# 10_USB_HDMI.net
KiCad netlist of a schematic drawn in Altium Designer
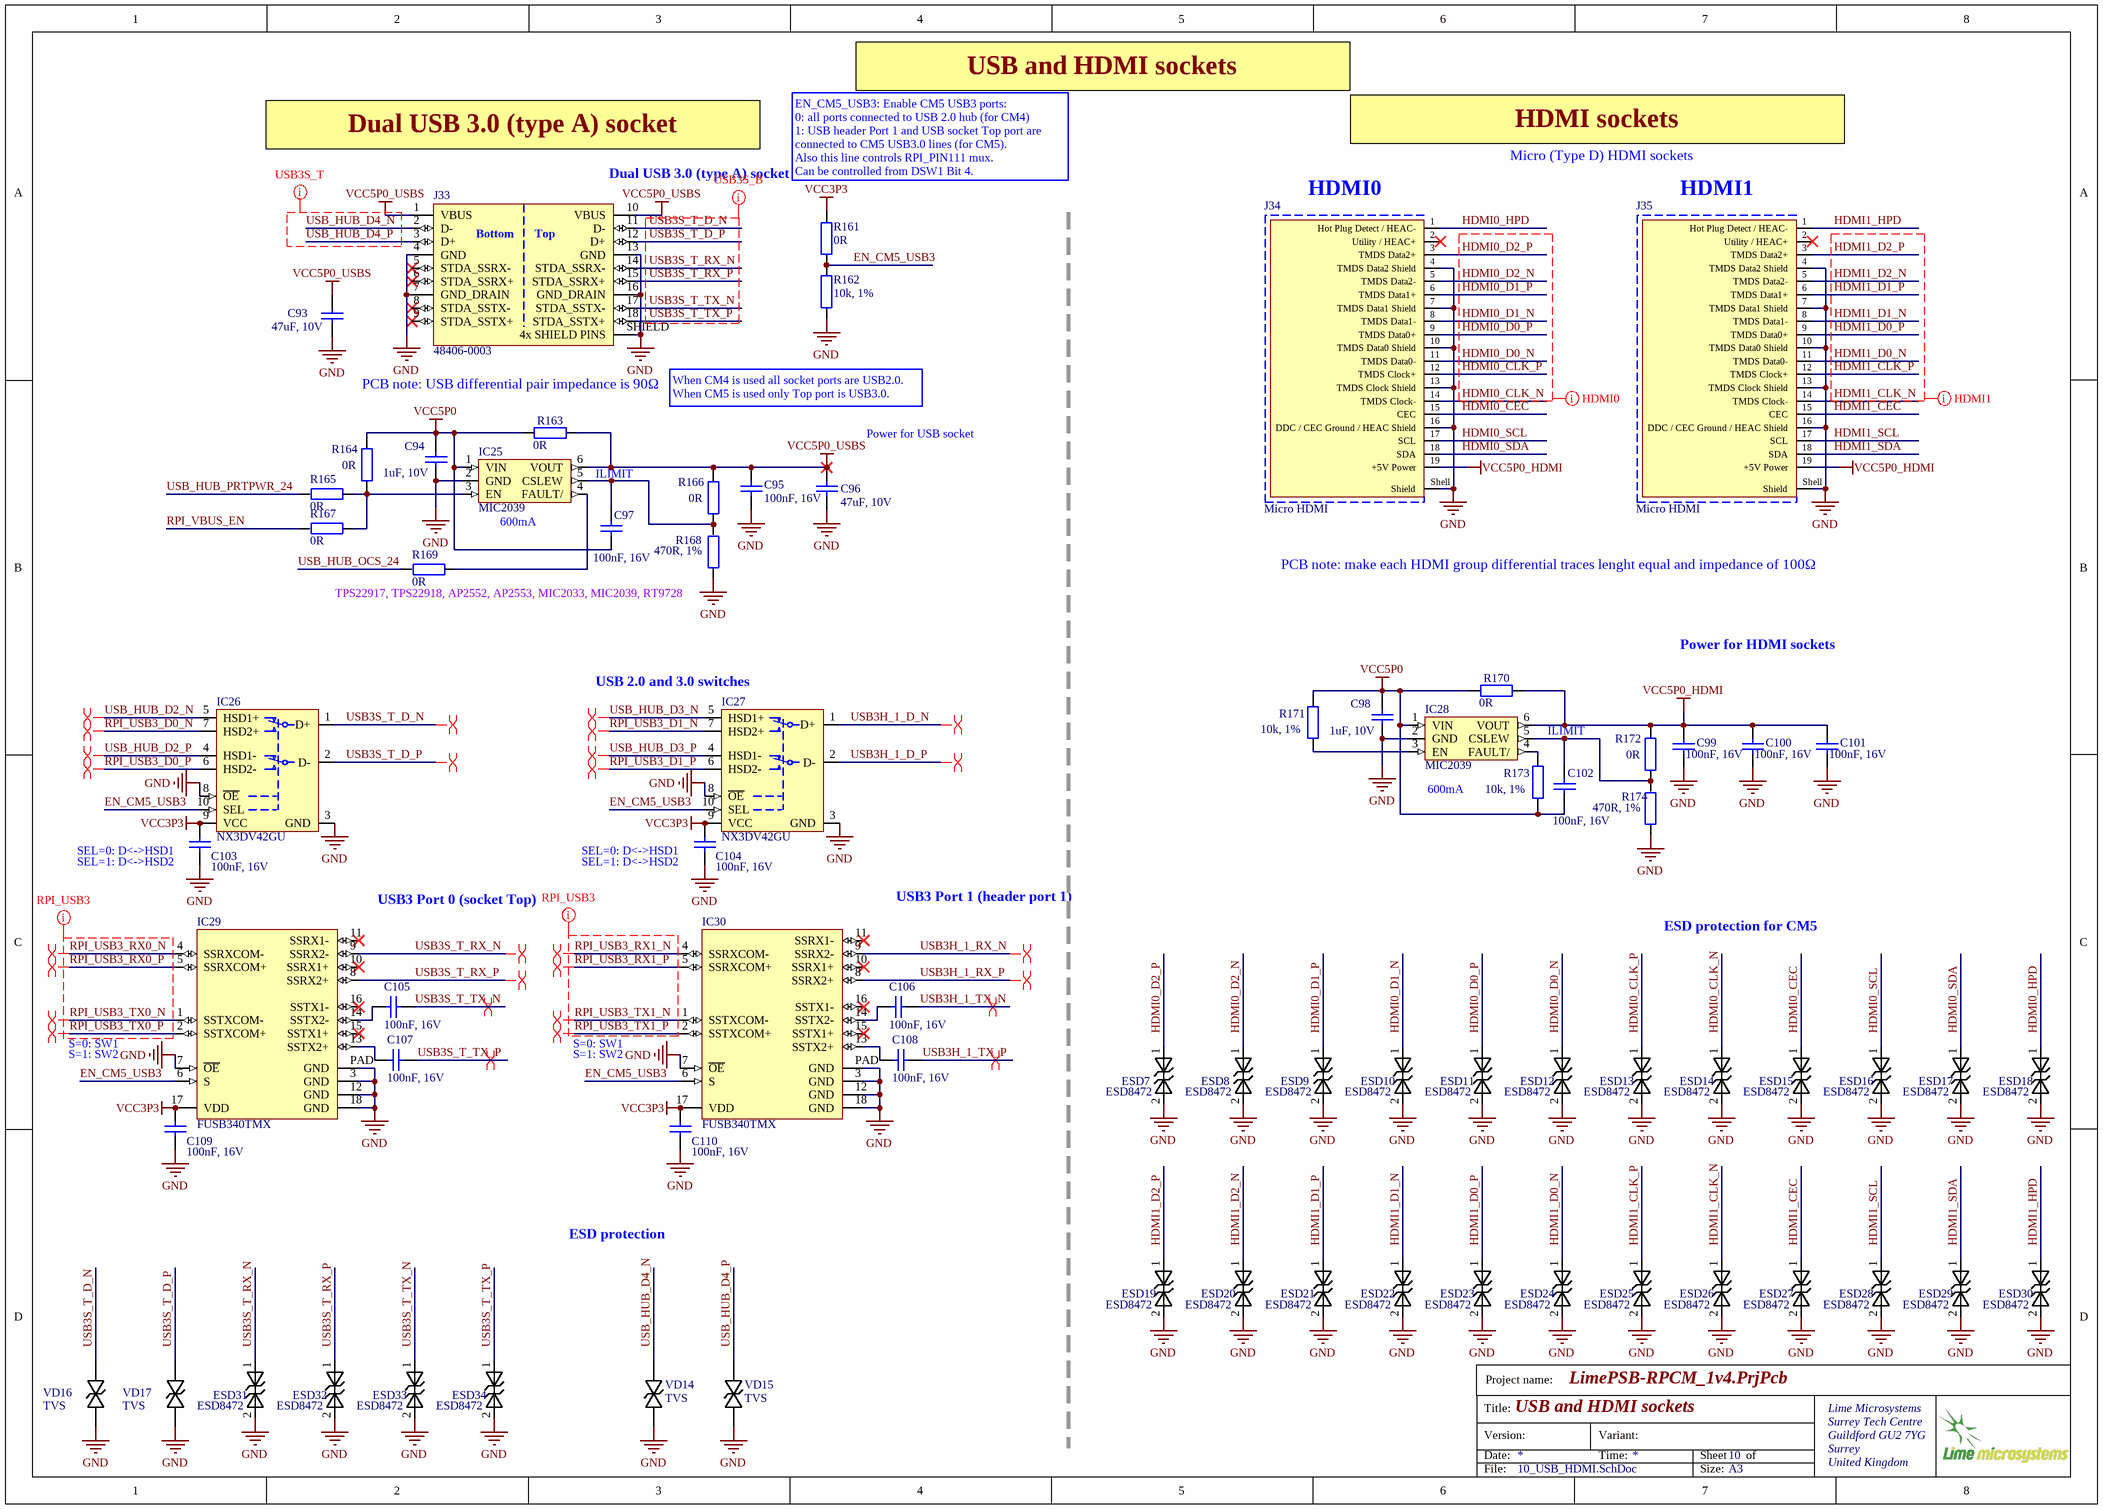
[diagram p0: 10_USB_HDMI.SchDoc]

(export (version "E")
  (design (tool "Eeschema 10.0.6"))
  (components
    (comp (ref "C93")
      (value "47uF, 10V")
      (footprint "CAP1206")
      (fields (field (name "TOLERANCE") "±20%") (field (name "MANUFACTURER") "TDK Corporation"))
      (libsource (lib "LimeFPGAboard_schLib") (part "Cap_1206"))
    )
    (comp (ref "C94")
      (value "1uF, 10V")
      (footprint "CAP0402")
      (fields (field (name "MANUFACTURER") "Yageo"))
      (libsource (lib "") (part "Cap_0402_1"))
    )
    (comp (ref "C95")
      (value "100nF, 16V")
      (footprint "CAP0402")
      (fields
        (field (name "MANUFACTURER") "Murata Electronics")
        (field (name "TOLERANCE") "10 %")
        (field (name "MANUFACTURER PART NUMBER") "GRM155R71C104KA88D")
      )
      (libsource (lib "") (part "Cap_0402_1"))
    )
    (comp (ref "C96")
      (value "47uF, 10V")
      (footprint "CAP1206")
      (fields (field (name "TOLERANCE") "±20%") (field (name "MANUFACTURER") "TDK Corporation"))
      (libsource (lib "LimeFPGAboard_schLib") (part "Cap_1206"))
    )
    (comp (ref "C97")
      (value "100nF, 16V")
      (footprint "CAP0402")
      (fields
        (field (name "MANUFACTURER") "Murata Electronics")
        (field (name "TOLERANCE") "10 %")
        (field (name "MANUFACTURER PART NUMBER") "GRM155R71C104KA88D")
      )
      (libsource (lib "") (part "Cap_0402_1"))
    )
    (comp (ref "C98")
      (value "1uF, 10V")
      (footprint "CAP0402")
      (fields (field (name "MANUFACTURER") "Yageo"))
      (libsource (lib "") (part "Cap_0402_1"))
    )
    (comp (ref "C99")
      (value "100nF, 16V")
      (footprint "CAP0402")
      (fields
        (field (name "MANUFACTURER") "Murata Electronics")
        (field (name "TOLERANCE") "10 %")
        (field (name "MANUFACTURER PART NUMBER") "GRM155R71C104KA88D")
      )
      (libsource (lib "") (part "Cap_0402_1"))
    )
    (comp (ref "C100")
      (value "100nF, 16V")
      (footprint "CAP0402")
      (fields
        (field (name "MANUFACTURER") "Murata Electronics")
        (field (name "TOLERANCE") "10 %")
        (field (name "MANUFACTURER PART NUMBER") "GRM155R71C104KA88D")
      )
      (libsource (lib "") (part "Cap_0402_1"))
    )
    (comp (ref "C101")
      (value "100nF, 16V")
      (footprint "CAP0402")
      (fields
        (field (name "MANUFACTURER") "Murata Electronics")
        (field (name "TOLERANCE") "10 %")
        (field (name "MANUFACTURER PART NUMBER") "GRM155R71C104KA88D")
      )
      (libsource (lib "") (part "Cap_0402_1"))
    )
    (comp (ref "C102")
      (value "100nF, 16V")
      (footprint "CAP0402")
      (fields
        (field (name "MANUFACTURER") "Murata Electronics")
        (field (name "TOLERANCE") "10 %")
        (field (name "MANUFACTURER PART NUMBER") "GRM155R71C104KA88D")
      )
      (libsource (lib "") (part "Cap_0402_1"))
    )
    (comp (ref "C103")
      (value "100nF, 16V")
      (footprint "CAP0402")
      (fields
        (field (name "MANUFACTURER") "Murata Electronics")
        (field (name "TOLERANCE") "10 %")
        (field (name "MANUFACTURER PART NUMBER") "GRM155R71C104KA88D")
      )
      (libsource (lib "LimeMicroAltiumLib_schLib") (part "Cap_0402"))
    )
    (comp (ref "C104")
      (value "100nF, 16V")
      (footprint "CAP0402")
      (fields
        (field (name "MANUFACTURER") "Murata Electronics")
        (field (name "TOLERANCE") "10 %")
        (field (name "MANUFACTURER PART NUMBER") "GRM155R71C104KA88D")
      )
      (libsource (lib "LimeMicroAltiumLib_schLib") (part "Cap_0402"))
    )
    (comp (ref "C105")
      (value "100nF, 16V")
      (footprint "CAP0402")
      (fields
        (field (name "MANUFACTURER") "Murata Electronics")
        (field (name "TOLERANCE") "10 %")
        (field (name "MANUFACTURER PART NUMBER") "GRM155R71C104KA88D")
      )
      (libsource (lib "LimeMicroAltiumLib_schLib") (part "Cap_0402"))
    )
    (comp (ref "C106")
      (value "100nF, 16V")
      (footprint "CAP0402")
      (fields
        (field (name "MANUFACTURER") "Murata Electronics")
        (field (name "TOLERANCE") "10 %")
        (field (name "MANUFACTURER PART NUMBER") "GRM155R71C104KA88D")
      )
      (libsource (lib "LimeMicroAltiumLib_schLib") (part "Cap_0402"))
    )
    (comp (ref "C107")
      (value "100nF, 16V")
      (footprint "CAP0402")
      (fields
        (field (name "MANUFACTURER") "Murata Electronics")
        (field (name "TOLERANCE") "10 %")
        (field (name "MANUFACTURER PART NUMBER") "GRM155R71C104KA88D")
      )
      (libsource (lib "LimeMicroAltiumLib_schLib") (part "Cap_0402"))
    )
    (comp (ref "C108")
      (value "100nF, 16V")
      (footprint "CAP0402")
      (fields
        (field (name "MANUFACTURER") "Murata Electronics")
        (field (name "TOLERANCE") "10 %")
        (field (name "MANUFACTURER PART NUMBER") "GRM155R71C104KA88D")
      )
      (libsource (lib "LimeMicroAltiumLib_schLib") (part "Cap_0402"))
    )
    (comp (ref "C109")
      (value "100nF, 16V")
      (footprint "CAP0402")
      (fields
        (field (name "MANUFACTURER") "Murata Electronics")
        (field (name "TOLERANCE") "10 %")
        (field (name "MANUFACTURER PART NUMBER") "GRM155R71C104KA88D")
      )
      (libsource (lib "LimeMicroAltiumLib_schLib") (part "Cap_0402"))
    )
    (comp (ref "C110")
      (value "100nF, 16V")
      (footprint "CAP0402")
      (fields
        (field (name "MANUFACTURER") "Murata Electronics")
        (field (name "TOLERANCE") "10 %")
        (field (name "MANUFACTURER PART NUMBER") "GRM155R71C104KA88D")
      )
      (libsource (lib "LimeMicroAltiumLib_schLib") (part "Cap_0402"))
    )
    (comp (ref "ESD7")
      (value "ESD8472")
      (footprint "ESD8472_X3DFN2")
      (fields (field (name "MANUFACTURER") "ON Semiconductor"))
      (libsource (lib "LimeMicroAltiumLib_schLib") (part "ESD8472"))
    )
    (comp (ref "ESD8")
      (value "ESD8472")
      (footprint "ESD8472_X3DFN2")
      (fields (field (name "MANUFACTURER") "ON Semiconductor"))
      (libsource (lib "LimeMicroAltiumLib_schLib") (part "ESD8472"))
    )
    (comp (ref "ESD9")
      (value "ESD8472")
      (footprint "ESD8472_X3DFN2")
      (fields (field (name "MANUFACTURER") "ON Semiconductor"))
      (libsource (lib "LimeMicroAltiumLib_schLib") (part "ESD8472"))
    )
    (comp (ref "ESD10")
      (value "ESD8472")
      (footprint "ESD8472_X3DFN2")
      (fields (field (name "MANUFACTURER") "ON Semiconductor"))
      (libsource (lib "LimeMicroAltiumLib_schLib") (part "ESD8472"))
    )
    (comp (ref "ESD11")
      (value "ESD8472")
      (footprint "ESD8472_X3DFN2")
      (fields (field (name "MANUFACTURER") "ON Semiconductor"))
      (libsource (lib "LimeMicroAltiumLib_schLib") (part "ESD8472"))
    )
    (comp (ref "ESD12")
      (value "ESD8472")
      (footprint "ESD8472_X3DFN2")
      (fields (field (name "MANUFACTURER") "ON Semiconductor"))
      (libsource (lib "LimeMicroAltiumLib_schLib") (part "ESD8472"))
    )
    (comp (ref "ESD13")
      (value "ESD8472")
      (footprint "ESD8472_X3DFN2")
      (fields (field (name "MANUFACTURER") "ON Semiconductor"))
      (libsource (lib "LimeMicroAltiumLib_schLib") (part "ESD8472"))
    )
    (comp (ref "ESD14")
      (value "ESD8472")
      (footprint "ESD8472_X3DFN2")
      (fields (field (name "MANUFACTURER") "ON Semiconductor"))
      (libsource (lib "LimeMicroAltiumLib_schLib") (part "ESD8472"))
    )
    (comp (ref "ESD15")
      (value "ESD8472")
      (footprint "ESD8472_X3DFN2")
      (fields (field (name "MANUFACTURER") "ON Semiconductor"))
      (libsource (lib "LimeMicroAltiumLib_schLib") (part "ESD8472"))
    )
    (comp (ref "ESD16")
      (value "ESD8472")
      (footprint "ESD8472_X3DFN2")
      (fields (field (name "MANUFACTURER") "ON Semiconductor"))
      (libsource (lib "LimeMicroAltiumLib_schLib") (part "ESD8472"))
    )
    (comp (ref "ESD17")
      (value "ESD8472")
      (footprint "ESD8472_X3DFN2")
      (fields (field (name "MANUFACTURER") "ON Semiconductor"))
      (libsource (lib "LimeMicroAltiumLib_schLib") (part "ESD8472"))
    )
    (comp (ref "ESD18")
      (value "ESD8472")
      (footprint "ESD8472_X3DFN2")
      (fields (field (name "MANUFACTURER") "ON Semiconductor"))
      (libsource (lib "LimeMicroAltiumLib_schLib") (part "ESD8472"))
    )
    (comp (ref "ESD19")
      (value "ESD8472")
      (footprint "ESD8472_X3DFN2")
      (fields (field (name "MANUFACTURER") "ON Semiconductor"))
      (libsource (lib "LimeMicroAltiumLib_schLib") (part "ESD8472"))
    )
    (comp (ref "ESD20")
      (value "ESD8472")
      (footprint "ESD8472_X3DFN2")
      (fields (field (name "MANUFACTURER") "ON Semiconductor"))
      (libsource (lib "LimeMicroAltiumLib_schLib") (part "ESD8472"))
    )
    (comp (ref "ESD21")
      (value "ESD8472")
      (footprint "ESD8472_X3DFN2")
      (fields (field (name "MANUFACTURER") "ON Semiconductor"))
      (libsource (lib "LimeMicroAltiumLib_schLib") (part "ESD8472"))
    )
    (comp (ref "ESD22")
      (value "ESD8472")
      (footprint "ESD8472_X3DFN2")
      (fields (field (name "MANUFACTURER") "ON Semiconductor"))
      (libsource (lib "LimeMicroAltiumLib_schLib") (part "ESD8472"))
    )
    (comp (ref "ESD23")
      (value "ESD8472")
      (footprint "ESD8472_X3DFN2")
      (fields (field (name "MANUFACTURER") "ON Semiconductor"))
      (libsource (lib "LimeMicroAltiumLib_schLib") (part "ESD8472"))
    )
    (comp (ref "ESD24")
      (value "ESD8472")
      (footprint "ESD8472_X3DFN2")
      (fields (field (name "MANUFACTURER") "ON Semiconductor"))
      (libsource (lib "LimeMicroAltiumLib_schLib") (part "ESD8472"))
    )
    (comp (ref "ESD25")
      (value "ESD8472")
      (footprint "ESD8472_X3DFN2")
      (fields (field (name "MANUFACTURER") "ON Semiconductor"))
      (libsource (lib "LimeMicroAltiumLib_schLib") (part "ESD8472"))
    )
    (comp (ref "ESD26")
      (value "ESD8472")
      (footprint "ESD8472_X3DFN2")
      (fields (field (name "MANUFACTURER") "ON Semiconductor"))
      (libsource (lib "LimeMicroAltiumLib_schLib") (part "ESD8472"))
    )
    (comp (ref "ESD27")
      (value "ESD8472")
      (footprint "ESD8472_X3DFN2")
      (fields (field (name "MANUFACTURER") "ON Semiconductor"))
      (libsource (lib "LimeMicroAltiumLib_schLib") (part "ESD8472"))
    )
    (comp (ref "ESD28")
      (value "ESD8472")
      (footprint "ESD8472_X3DFN2")
      (fields (field (name "MANUFACTURER") "ON Semiconductor"))
      (libsource (lib "LimeMicroAltiumLib_schLib") (part "ESD8472"))
    )
    (comp (ref "ESD29")
      (value "ESD8472")
      (footprint "ESD8472_X3DFN2")
      (fields (field (name "MANUFACTURER") "ON Semiconductor"))
      (libsource (lib "LimeMicroAltiumLib_schLib") (part "ESD8472"))
    )
    (comp (ref "ESD30")
      (value "ESD8472")
      (footprint "ESD8472_X3DFN2")
      (fields (field (name "MANUFACTURER") "ON Semiconductor"))
      (libsource (lib "LimeMicroAltiumLib_schLib") (part "ESD8472"))
    )
    (comp (ref "ESD31")
      (value "ESD8472")
      (footprint "ESD8472_X3DFN2")
      (fields (field (name "MANUFACTURER") "ON Semiconductor"))
      (libsource (lib "LimeMicroAltiumLib_schLib") (part "ESD8472"))
    )
    (comp (ref "ESD32")
      (value "ESD8472")
      (footprint "ESD8472_X3DFN2")
      (fields (field (name "MANUFACTURER") "ON Semiconductor"))
      (libsource (lib "LimeMicroAltiumLib_schLib") (part "ESD8472"))
    )
    (comp (ref "ESD33")
      (value "ESD8472")
      (footprint "ESD8472_X3DFN2")
      (fields (field (name "MANUFACTURER") "ON Semiconductor"))
      (libsource (lib "LimeMicroAltiumLib_schLib") (part "ESD8472"))
    )
    (comp (ref "ESD34")
      (value "ESD8472")
      (footprint "ESD8472_X3DFN2")
      (fields (field (name "MANUFACTURER") "ON Semiconductor"))
      (libsource (lib "LimeMicroAltiumLib_schLib") (part "ESD8472"))
    )
    (comp (ref "IC25")
      (value "MIC2039")
      (footprint "SOT23-6")
      (fields (field (name "MANUFACTURER") "Microchip"))
      (libsource (lib "LimeMicroAltiumLib_schLib_r04") (part "MIC2033_power_switch"))
    )
    (comp (ref "IC26")
      (value "NX3DV42GU")
      (footprint "FSUSB42UMX")
      (fields (field (name "MANUFACTURER") "NXP Semiconductors"))
      (libsource (lib "LimeMicroAltiumLib_schLib_r01") (part "FSUSB42UMX"))
    )
    (comp (ref "IC27")
      (value "NX3DV42GU")
      (footprint "FSUSB42UMX")
      (fields (field (name "MANUFACTURER") "NXP Semiconductors"))
      (libsource (lib "LimeMicroAltiumLib_schLib_r01") (part "FSUSB42UMX"))
    )
    (comp (ref "IC28")
      (value "MIC2039")
      (footprint "SOT23-6")
      (fields (field (name "MANUFACTURER") "Microchip"))
      (libsource (lib "LimeMicroAltiumLib_schLib_r04") (part "MIC2033_power_switch"))
    )
    (comp (ref "IC29")
      (value "FUSB340TMX")
      (footprint "FUSB340TMX_USB_switch_18-XFQFN")
      (fields (field (name "MANUFACTURER") "ON Semiconductor / Fairchild"))
      (libsource (lib "LimeMicroAltiumLib") (part "FUSB340TMX_USB_switch"))
    )
    (comp (ref "IC30")
      (value "FUSB340TMX")
      (footprint "FUSB340TMX_USB_switch_18-XFQFN")
      (fields (field (name "MANUFACTURER") "ON Semiconductor / Fairchild"))
      (libsource (lib "LimeMicroAltiumLib") (part "FUSB340TMX_USB_switch"))
    )
    (comp (ref "J33")
      (value "48406-0003")
      (footprint "Dual_USB_48406-0003_Molex")
      (fields (field (name "MANUFACTURER") "Molex"))
      (libsource (lib "LimeMicroAltiumLib") (part "Dual_USB_48406-0003_Molex"))
    )
    (comp (ref "J34")
      (value "Micro HDMI")
      (footprint "MICRO_HDMI_Wurth_685119248123")
      (description "Also compatible with Molex 0467651301 and Amphenol 10118242-001RLF")
      (fields (field (name "MANUFACTURER") "Wurth Electronics"))
      (libsource (lib "LimeMicroAltiumLib") (part "MICRO_HDMI_Wurth_685119248123"))
    )
    (comp (ref "J35")
      (value "Micro HDMI")
      (footprint "MICRO_HDMI_Wurth_685119248123")
      (description "Also compatible with Molex 0467651301 and Amphenol 10118242-001RLF")
      (fields (field (name "MANUFACTURER") "Wurth Electronics"))
      (libsource (lib "LimeMicroAltiumLib") (part "MICRO_HDMI_Wurth_685119248123"))
    )
    (comp (ref "R161")
      (value "0R")
      (footprint "RES0402")
      (fields (field (name "MANUFACTURER") "Yageo") (field (name "TOLERANCE") "Jumper"))
      (libsource (lib "") (part "Res_0402_1"))
    )
    (comp (ref "R162")
      (value "10k, 1%")
      (footprint "RES0402")
      (fields (field (name "MANUFACTURER") "Yageo") (field (name "TOLERANCE") "±1%"))
      (libsource (lib "") (part "Res_0402_1"))
    )
    (comp (ref "R163")
      (value "0R")
      (footprint "RES0402")
      (fields (field (name "MANUFACTURER") "Yageo") (field (name "TOLERANCE") "Jumper"))
      (libsource (lib "LimeMicroAltiumLib_schLib") (part "Res_0402"))
    )
    (comp (ref "R164")
      (value "0R")
      (footprint "RES0402")
      (fields (field (name "MANUFACTURER") "Yageo") (field (name "TOLERANCE") "Jumper"))
      (libsource (lib "LimeMicroAltiumLib_schLib") (part "Res_0402"))
    )
    (comp (ref "R165")
      (value "0R")
      (footprint "RES0402")
      (fields (field (name "MANUFACTURER") "Yageo") (field (name "TOLERANCE") "Jumper"))
      (libsource (lib "LimeMicroAltiumLib_schLib") (part "Res_0402"))
    )
    (comp (ref "R166")
      (value "0R")
      (footprint "RES0402")
      (fields (field (name "MANUFACTURER") "Yageo") (field (name "TOLERANCE") "Jumper"))
      (libsource (lib "LimeMicroAltiumLib_schLib") (part "Res_0402"))
    )
    (comp (ref "R167")
      (value "0R")
      (footprint "RES0402")
      (fields (field (name "MANUFACTURER") "Yageo") (field (name "TOLERANCE") "Jumper"))
      (libsource (lib "LimeMicroAltiumLib_schLib") (part "Res_0402"))
    )
    (comp (ref "R168")
      (value "470R, 1%")
      (footprint "RES0402")
      (fields (field (name "TOLERANCE") "1%") (field (name "MANUFACTURER") "Yageo"))
      (libsource (lib "LimeMicroAltiumLib_schLib") (part "Res_0402"))
    )
    (comp (ref "R169")
      (value "0R")
      (footprint "RES0402")
      (fields (field (name "MANUFACTURER") "Yageo") (field (name "TOLERANCE") "Jumper"))
      (libsource (lib "LimeMicroAltiumLib_schLib") (part "Res_0402"))
    )
    (comp (ref "R170")
      (value "0R")
      (footprint "RES0402")
      (fields (field (name "MANUFACTURER") "Yageo") (field (name "TOLERANCE") "Jumper"))
      (libsource (lib "LimeMicroAltiumLib_schLib") (part "Res_0402"))
    )
    (comp (ref "R171")
      (value "10k, 1%")
      (footprint "RES0402")
      (fields (field (name "MANUFACTURER") "Yageo") (field (name "TOLERANCE") "±1%"))
      (libsource (lib "") (part "Res_0402_1"))
    )
    (comp (ref "R172")
      (value "0R")
      (footprint "RES0402")
      (fields (field (name "MANUFACTURER") "Yageo") (field (name "TOLERANCE") "Jumper"))
      (libsource (lib "LimeMicroAltiumLib_schLib") (part "Res_0402"))
    )
    (comp (ref "R173")
      (value "10k, 1%")
      (footprint "RES0402")
      (fields (field (name "MANUFACTURER") "Yageo") (field (name "TOLERANCE") "±1%"))
      (libsource (lib "") (part "Res_0402_1"))
    )
    (comp (ref "R174")
      (value "470R, 1%")
      (footprint "RES0402")
      (fields (field (name "TOLERANCE") "1%") (field (name "MANUFACTURER") "Yageo"))
      (libsource (lib "LimeMicroAltiumLib_schLib") (part "Res_0402"))
    )
    (comp (ref "VD14")
      (value "TVS")
      (footprint "SOD323")
      (fields
        (field (name "MANUFACTURER PART NUMBER") "SD03LCC")
        (field (name "MANUFACTURER") "Sangdest Microelectronics")
      )
      (libsource (lib "LimeNet-Micro_2v1-SDR") (part "DIODE_TVS"))
    )
    (comp (ref "VD15")
      (value "TVS")
      (footprint "SOD323")
      (fields
        (field (name "MANUFACTURER PART NUMBER") "SD03LCC")
        (field (name "MANUFACTURER") "Sangdest Microelectronics")
      )
      (libsource (lib "LimeNet-Micro_2v1-SDR") (part "DIODE_TVS"))
    )
    (comp (ref "VD16")
      (value "TVS")
      (footprint "SOD323")
      (fields
        (field (name "MANUFACTURER PART NUMBER") "SD03LCC")
        (field (name "MANUFACTURER") "Sangdest Microelectronics")
      )
      (libsource (lib "LimeNet-Micro_2v1-SDR") (part "DIODE_TVS"))
    )
    (comp (ref "VD17")
      (value "TVS")
      (footprint "SOD323")
      (fields
        (field (name "MANUFACTURER PART NUMBER") "SD03LCC")
        (field (name "MANUFACTURER") "Sangdest Microelectronics")
      )
      (libsource (lib "LimeNet-Micro_2v1-SDR") (part "DIODE_TVS"))
    )
  )
  (nets
    (net (code "1") (name "/EN_CM5_USB3") (class "Default")
      (node (ref "IC26") (pin "10") (pinfunction "SEL_10") (pintype "input"))
      (node (ref "IC27") (pin "10") (pinfunction "SEL_10") (pintype "input"))
      (node (ref "IC29") (pin "6") (pinfunction "S_6") (pintype "input"))
      (node (ref "IC30") (pin "6") (pinfunction "S_6") (pintype "input"))
      (node (ref "R161") (pin "1") (pinfunction "1_1") (pintype "passive"))
      (node (ref "R162") (pin "1") (pinfunction "1_1") (pintype "passive"))
    )
    (net (code "2") (name "/HDMI0_CEC") (class "Default")
      (node (ref "ESD15") (pin "1") (pinfunction "1_1") (pintype "passive"))
      (node (ref "J34") (pin "15") (pinfunction "CEC_15") (pintype "passive"))
    )
    (net (code "3") (name "/HDMI0_CLK_N") (class "Default")
      (node (ref "ESD14") (pin "1") (pinfunction "1_1") (pintype "passive"))
      (node (ref "J34") (pin "14") (pinfunction "TMDS_Clock-_14") (pintype "passive"))
    )
    (net (code "4") (name "/HDMI0_CLK_P") (class "Default")
      (node (ref "ESD13") (pin "1") (pinfunction "1_1") (pintype "passive"))
      (node (ref "J34") (pin "12") (pinfunction "TMDS_Clock+_12") (pintype "passive"))
    )
    (net (code "5") (name "/HDMI0_D0_N") (class "Default")
      (node (ref "ESD12") (pin "1") (pinfunction "1_1") (pintype "passive"))
      (node (ref "J34") (pin "11") (pinfunction "TMDS_Data0-_11") (pintype "passive"))
    )
    (net (code "6") (name "/HDMI0_D0_P") (class "Default")
      (node (ref "ESD11") (pin "1") (pinfunction "1_1") (pintype "passive"))
      (node (ref "J34") (pin "9") (pinfunction "TMDS_Data0+_9") (pintype "passive"))
    )
    (net (code "7") (name "/HDMI0_D1_N") (class "Default")
      (node (ref "ESD10") (pin "1") (pinfunction "1_1") (pintype "passive"))
      (node (ref "J34") (pin "8") (pinfunction "TMDS_Data1-_8") (pintype "passive"))
    )
    (net (code "8") (name "/HDMI0_D1_P") (class "Default")
      (node (ref "ESD9") (pin "1") (pinfunction "1_1") (pintype "passive"))
      (node (ref "J34") (pin "6") (pinfunction "TMDS_Data1+_6") (pintype "passive"))
    )
    (net (code "9") (name "/HDMI0_D2_N") (class "Default")
      (node (ref "ESD8") (pin "1") (pinfunction "1_1") (pintype "passive"))
      (node (ref "J34") (pin "5") (pinfunction "TMDS_Data2-_5") (pintype "passive"))
    )
    (net (code "10") (name "/HDMI0_D2_P") (class "Default")
      (node (ref "ESD7") (pin "1") (pinfunction "1_1") (pintype "passive"))
      (node (ref "J34") (pin "3") (pinfunction "TMDS_Data2+_3") (pintype "passive"))
    )
    (net (code "11") (name "/HDMI0_HPD") (class "Default")
      (node (ref "ESD18") (pin "1") (pinfunction "1_1") (pintype "passive"))
      (node (ref "J34") (pin "1") (pinfunction "Hot_Plug_Detect_/_HEAC-_1") (pintype "passive"))
    )
    (net (code "12") (name "/HDMI0_SCL") (class "Default")
      (node (ref "ESD16") (pin "1") (pinfunction "1_1") (pintype "passive"))
      (node (ref "J34") (pin "17") (pinfunction "SCL_17") (pintype "passive"))
    )
    (net (code "13") (name "/HDMI0_SDA") (class "Default")
      (node (ref "ESD17") (pin "1") (pinfunction "1_1") (pintype "passive"))
      (node (ref "J34") (pin "18") (pinfunction "SDA_18") (pintype "passive"))
    )
    (net (code "14") (name "/HDMI1_CEC") (class "Default")
      (node (ref "ESD27") (pin "1") (pinfunction "1_1") (pintype "passive"))
      (node (ref "J35") (pin "15") (pinfunction "CEC_15") (pintype "passive"))
    )
    (net (code "15") (name "/HDMI1_CLK_N") (class "Default")
      (node (ref "ESD26") (pin "1") (pinfunction "1_1") (pintype "passive"))
      (node (ref "J35") (pin "14") (pinfunction "TMDS_Clock-_14") (pintype "passive"))
    )
    (net (code "16") (name "/HDMI1_CLK_P") (class "Default")
      (node (ref "ESD25") (pin "1") (pinfunction "1_1") (pintype "passive"))
      (node (ref "J35") (pin "12") (pinfunction "TMDS_Clock+_12") (pintype "passive"))
    )
    (net (code "17") (name "/HDMI1_D0_N") (class "Default")
      (node (ref "ESD24") (pin "1") (pinfunction "1_1") (pintype "passive"))
      (node (ref "J35") (pin "11") (pinfunction "TMDS_Data0-_11") (pintype "passive"))
    )
    (net (code "18") (name "/HDMI1_D0_P") (class "Default")
      (node (ref "ESD23") (pin "1") (pinfunction "1_1") (pintype "passive"))
      (node (ref "J35") (pin "9") (pinfunction "TMDS_Data0+_9") (pintype "passive"))
    )
    (net (code "19") (name "/HDMI1_D1_N") (class "Default")
      (node (ref "ESD22") (pin "1") (pinfunction "1_1") (pintype "passive"))
      (node (ref "J35") (pin "8") (pinfunction "TMDS_Data1-_8") (pintype "passive"))
    )
    (net (code "20") (name "/HDMI1_D1_P") (class "Default")
      (node (ref "ESD21") (pin "1") (pinfunction "1_1") (pintype "passive"))
      (node (ref "J35") (pin "6") (pinfunction "TMDS_Data1+_6") (pintype "passive"))
    )
    (net (code "21") (name "/HDMI1_D2_N") (class "Default")
      (node (ref "ESD20") (pin "1") (pinfunction "1_1") (pintype "passive"))
      (node (ref "J35") (pin "5") (pinfunction "TMDS_Data2-_5") (pintype "passive"))
    )
    (net (code "22") (name "/HDMI1_D2_P") (class "Default")
      (node (ref "ESD19") (pin "1") (pinfunction "1_1") (pintype "passive"))
      (node (ref "J35") (pin "3") (pinfunction "TMDS_Data2+_3") (pintype "passive"))
    )
    (net (code "23") (name "/HDMI1_HPD") (class "Default")
      (node (ref "ESD30") (pin "1") (pinfunction "1_1") (pintype "passive"))
      (node (ref "J35") (pin "1") (pinfunction "Hot_Plug_Detect_/_HEAC-_1") (pintype "passive"))
    )
    (net (code "24") (name "/HDMI1_SCL") (class "Default")
      (node (ref "ESD28") (pin "1") (pinfunction "1_1") (pintype "passive"))
      (node (ref "J35") (pin "17") (pinfunction "SCL_17") (pintype "passive"))
    )
    (net (code "25") (name "/HDMI1_SDA") (class "Default")
      (node (ref "ESD29") (pin "1") (pinfunction "1_1") (pintype "passive"))
      (node (ref "J35") (pin "18") (pinfunction "SDA_18") (pintype "passive"))
    )
    (net (code "26") (name "/RPI_USB3_D0_N") (class "Default")
      (node (ref "IC26") (pin "7") (pinfunction "HSD2+_7") (pintype "passive"))
    )
    (net (code "27") (name "/RPI_USB3_D0_P") (class "Default")
      (node (ref "IC26") (pin "6") (pinfunction "HSD2-_6") (pintype "passive"))
    )
    (net (code "28") (name "/RPI_USB3_D1_N") (class "Default")
      (node (ref "IC27") (pin "7") (pinfunction "HSD2+_7") (pintype "passive"))
    )
    (net (code "29") (name "/RPI_USB3_D1_P") (class "Default")
      (node (ref "IC27") (pin "6") (pinfunction "HSD2-_6") (pintype "passive"))
    )
    (net (code "30") (name "/RPI_USB3_RX0_N") (class "Default")
      (node (ref "IC29") (pin "4") (pinfunction "SSRXCOM-_4") (pintype "bidirectional"))
    )
    (net (code "31") (name "/RPI_USB3_RX0_P") (class "Default")
      (node (ref "IC29") (pin "5") (pinfunction "SSRXCOM+_5") (pintype "bidirectional"))
    )
    (net (code "32") (name "/RPI_USB3_RX1_N") (class "Default")
      (node (ref "IC30") (pin "4") (pinfunction "SSRXCOM-_4") (pintype "bidirectional"))
    )
    (net (code "33") (name "/RPI_USB3_RX1_P") (class "Default")
      (node (ref "IC30") (pin "5") (pinfunction "SSRXCOM+_5") (pintype "bidirectional"))
    )
    (net (code "34") (name "/RPI_USB3_TX0_N") (class "Default")
      (node (ref "IC29") (pin "1") (pinfunction "SSTXCOM-_1") (pintype "bidirectional"))
    )
    (net (code "35") (name "/RPI_USB3_TX0_P") (class "Default")
      (node (ref "IC29") (pin "2") (pinfunction "SSTXCOM+_2") (pintype "bidirectional"))
    )
    (net (code "36") (name "/RPI_USB3_TX1_N") (class "Default")
      (node (ref "IC30") (pin "1") (pinfunction "SSTXCOM-_1") (pintype "bidirectional"))
    )
    (net (code "37") (name "/RPI_USB3_TX1_P") (class "Default")
      (node (ref "IC30") (pin "2") (pinfunction "SSTXCOM+_2") (pintype "bidirectional"))
    )
    (net (code "38") (name "/RPI_VBUS_EN") (class "Default")
      (node (ref "R167") (pin "2") (pinfunction "2_2") (pintype "passive"))
    )
    (net (code "39") (name "/USB3H_1_D_N") (class "Default")
      (node (ref "IC27") (pin "1") (pinfunction "D+_1") (pintype "passive"))
    )
    (net (code "40") (name "/USB3H_1_D_P") (class "Default")
      (node (ref "IC27") (pin "2") (pinfunction "D-_2") (pintype "passive"))
    )
    (net (code "41") (name "/USB3H_1_RX_N") (class "Default")
      (node (ref "IC30") (pin "9") (pinfunction "SSRX2-_9") (pintype "bidirectional"))
    )
    (net (code "42") (name "/USB3H_1_RX_P") (class "Default")
      (node (ref "IC30") (pin "8") (pinfunction "SSRX2+_8") (pintype "bidirectional"))
    )
    (net (code "43") (name "/USB3H_1_TX_N") (class "Default")
      (node (ref "C106") (pin "2") (pinfunction "2_2") (pintype "passive"))
    )
    (net (code "44") (name "/USB3H_1_TX_P") (class "Default")
      (node (ref "C108") (pin "2") (pinfunction "2_2") (pintype "passive"))
    )
    (net (code "45") (name "/USB3S_T_D_N") (class "Default")
      (node (ref "IC26") (pin "1") (pinfunction "D+_1") (pintype "passive"))
      (node (ref "J33") (pin "11") (pinfunction "D-_11") (pintype "bidirectional"))
      (node (ref "VD16") (pin "A") (pinfunction "A_A") (pintype "passive"))
    )
    (net (code "46") (name "/USB3S_T_D_P") (class "Default")
      (node (ref "IC26") (pin "2") (pinfunction "D-_2") (pintype "passive"))
      (node (ref "J33") (pin "12") (pinfunction "D+_12") (pintype "bidirectional"))
      (node (ref "VD17") (pin "A") (pinfunction "A_A") (pintype "passive"))
    )
    (net (code "47") (name "/USB3S_T_RX_N") (class "Default")
      (node (ref "ESD31") (pin "1") (pinfunction "1_1") (pintype "passive"))
      (node (ref "IC29") (pin "9") (pinfunction "SSRX2-_9") (pintype "bidirectional"))
      (node (ref "J33") (pin "14") (pinfunction "STDA_SSRX-_14") (pintype "bidirectional"))
    )
    (net (code "48") (name "/USB3S_T_RX_P") (class "Default")
      (node (ref "ESD32") (pin "1") (pinfunction "1_1") (pintype "passive"))
      (node (ref "IC29") (pin "8") (pinfunction "SSRX2+_8") (pintype "bidirectional"))
      (node (ref "J33") (pin "15") (pinfunction "STDA_SSRX+_15") (pintype "bidirectional"))
    )
    (net (code "49") (name "/USB3S_T_TX_N") (class "Default")
      (node (ref "C105") (pin "2") (pinfunction "2_2") (pintype "passive"))
      (node (ref "ESD33") (pin "1") (pinfunction "1_1") (pintype "passive"))
      (node (ref "J33") (pin "17") (pinfunction "STDA_SSTX-_17") (pintype "bidirectional"))
    )
    (net (code "50") (name "/USB3S_T_TX_P") (class "Default")
      (node (ref "C107") (pin "2") (pinfunction "2_2") (pintype "passive"))
      (node (ref "ESD34") (pin "1") (pinfunction "1_1") (pintype "passive"))
      (node (ref "J33") (pin "18") (pinfunction "STDA_SSTX+_18") (pintype "bidirectional"))
    )
    (net (code "51") (name "/USB_HUB_D2_N") (class "Default")
      (node (ref "IC26") (pin "5") (pinfunction "HSD1+_5") (pintype "passive"))
    )
    (net (code "52") (name "/USB_HUB_D2_P") (class "Default")
      (node (ref "IC26") (pin "4") (pinfunction "HSD1-_4") (pintype "passive"))
    )
    (net (code "53") (name "/USB_HUB_D3_N") (class "Default")
      (node (ref "IC27") (pin "5") (pinfunction "HSD1+_5") (pintype "passive"))
    )
    (net (code "54") (name "/USB_HUB_D3_P") (class "Default")
      (node (ref "IC27") (pin "4") (pinfunction "HSD1-_4") (pintype "passive"))
    )
    (net (code "55") (name "/USB_HUB_D4_N") (class "Default")
      (node (ref "J33") (pin "2") (pinfunction "D-_2") (pintype "bidirectional"))
      (node (ref "VD14") (pin "A") (pinfunction "A_A") (pintype "passive"))
    )
    (net (code "56") (name "/USB_HUB_D4_P") (class "Default")
      (node (ref "J33") (pin "3") (pinfunction "D+_3") (pintype "bidirectional"))
      (node (ref "VD15") (pin "A") (pinfunction "A_A") (pintype "passive"))
    )
    (net (code "57") (name "/USB_HUB_OCS_24") (class "Default")
      (node (ref "R169") (pin "2") (pinfunction "2_2") (pintype "passive"))
    )
    (net (code "58") (name "/USB_HUB_PRTPWR_24") (class "Default")
      (node (ref "R165") (pin "2") (pinfunction "2_2") (pintype "passive"))
    )
    (net (code "59") (name "GND") (class "Default")
      (node (ref "C100") (pin "2") (pinfunction "2_2") (pintype "passive"))
      (node (ref "C101") (pin "2") (pinfunction "2_2") (pintype "passive"))
      (node (ref "C103") (pin "2") (pinfunction "2_2") (pintype "passive"))
      (node (ref "C104") (pin "2") (pinfunction "2_2") (pintype "passive"))
      (node (ref "C109") (pin "2") (pinfunction "2_2") (pintype "passive"))
      (node (ref "C110") (pin "2") (pinfunction "2_2") (pintype "passive"))
      (node (ref "C93") (pin "1") (pinfunction "1_1") (pintype "passive"))
      (node (ref "C94") (pin "2") (pinfunction "2_2") (pintype "passive"))
      (node (ref "C95") (pin "2") (pinfunction "2_2") (pintype "passive"))
      (node (ref "C96") (pin "1") (pinfunction "1_1") (pintype "passive"))
      (node (ref "C98") (pin "2") (pinfunction "2_2") (pintype "passive"))
      (node (ref "C99") (pin "2") (pinfunction "2_2") (pintype "passive"))
      (node (ref "ESD10") (pin "2") (pinfunction "2_2") (pintype "passive"))
      (node (ref "ESD11") (pin "2") (pinfunction "2_2") (pintype "passive"))
      (node (ref "ESD12") (pin "2") (pinfunction "2_2") (pintype "passive"))
      (node (ref "ESD13") (pin "2") (pinfunction "2_2") (pintype "passive"))
      (node (ref "ESD14") (pin "2") (pinfunction "2_2") (pintype "passive"))
      (node (ref "ESD15") (pin "2") (pinfunction "2_2") (pintype "passive"))
      (node (ref "ESD16") (pin "2") (pinfunction "2_2") (pintype "passive"))
      (node (ref "ESD17") (pin "2") (pinfunction "2_2") (pintype "passive"))
      (node (ref "ESD18") (pin "2") (pinfunction "2_2") (pintype "passive"))
      (node (ref "ESD19") (pin "2") (pinfunction "2_2") (pintype "passive"))
      (node (ref "ESD20") (pin "2") (pinfunction "2_2") (pintype "passive"))
      (node (ref "ESD21") (pin "2") (pinfunction "2_2") (pintype "passive"))
      (node (ref "ESD22") (pin "2") (pinfunction "2_2") (pintype "passive"))
      (node (ref "ESD23") (pin "2") (pinfunction "2_2") (pintype "passive"))
      (node (ref "ESD24") (pin "2") (pinfunction "2_2") (pintype "passive"))
      (node (ref "ESD25") (pin "2") (pinfunction "2_2") (pintype "passive"))
      (node (ref "ESD26") (pin "2") (pinfunction "2_2") (pintype "passive"))
      (node (ref "ESD27") (pin "2") (pinfunction "2_2") (pintype "passive"))
      (node (ref "ESD28") (pin "2") (pinfunction "2_2") (pintype "passive"))
      (node (ref "ESD29") (pin "2") (pinfunction "2_2") (pintype "passive"))
      (node (ref "ESD30") (pin "2") (pinfunction "2_2") (pintype "passive"))
      (node (ref "ESD31") (pin "2") (pinfunction "2_2") (pintype "passive"))
      (node (ref "ESD32") (pin "2") (pinfunction "2_2") (pintype "passive"))
      (node (ref "ESD33") (pin "2") (pinfunction "2_2") (pintype "passive"))
      (node (ref "ESD34") (pin "2") (pinfunction "2_2") (pintype "passive"))
      (node (ref "ESD7") (pin "2") (pinfunction "2_2") (pintype "passive"))
      (node (ref "ESD8") (pin "2") (pinfunction "2_2") (pintype "passive"))
      (node (ref "ESD9") (pin "2") (pinfunction "2_2") (pintype "passive"))
      (node (ref "IC25") (pin "2") (pinfunction "GND_2") (pintype "passive"))
      (node (ref "IC26") (pin "3") (pinfunction "GND_3") (pintype "passive"))
      (node (ref "IC26") (pin "8") (pinfunction "~{OE}_8") (pintype "input"))
      (node (ref "IC27") (pin "3") (pinfunction "GND_3") (pintype "passive"))
      (node (ref "IC27") (pin "8") (pinfunction "~{OE}_8") (pintype "input"))
      (node (ref "IC28") (pin "2") (pinfunction "GND_2") (pintype "passive"))
      (node (ref "IC29") (pin "12") (pinfunction "GND_12") (pintype "passive"))
      (node (ref "IC29") (pin "18") (pinfunction "GND_18") (pintype "passive"))
      (node (ref "IC29") (pin "3") (pinfunction "GND_3") (pintype "passive"))
      (node (ref "IC29") (pin "7") (pinfunction "~{OE}_7") (pintype "input"))
      (node (ref "IC29") (pin "PAD") (pinfunction "GND_PAD") (pintype "passive"))
      (node (ref "IC30") (pin "12") (pinfunction "GND_12") (pintype "passive"))
      (node (ref "IC30") (pin "18") (pinfunction "GND_18") (pintype "passive"))
      (node (ref "IC30") (pin "3") (pinfunction "GND_3") (pintype "passive"))
      (node (ref "IC30") (pin "7") (pinfunction "~{OE}_7") (pintype "input"))
      (node (ref "IC30") (pin "PAD") (pinfunction "GND_PAD") (pintype "passive"))
      (node (ref "J33") (pin "13") (pinfunction "GND_13") (pintype "power_in"))
      (node (ref "J33") (pin "16") (pinfunction "GND_DRAIN_16") (pintype "power_in"))
      (node (ref "J33") (pin "4") (pinfunction "GND_4") (pintype "power_in"))
      (node (ref "J33") (pin "7") (pinfunction "GND_DRAIN_7") (pintype "power_in"))
      (node (ref "J33") (pin "SHIELD") (pinfunction "4x_SHIELD_PINS_SHIELD") (pintype "power_in"))
      (node (ref "J34") (pin "10") (pinfunction "TMDS_Data0_Shield_10") (pintype "passive"))
      (node (ref "J34") (pin "13") (pinfunction "TMDS_Clock_Shield_13") (pintype "passive"))
      (node (ref "J34") (pin "16") (pinfunction "DDC_/_CEC_Ground_/_HEAC_Shield_16") (pintype "passive"))
      (node (ref "J34") (pin "4") (pinfunction "TMDS_Data2_Shield_4") (pintype "passive"))
      (node (ref "J34") (pin "7") (pinfunction "TMDS_Data1_Shield_7") (pintype "passive"))
      (node (ref "J34") (pin "Shell") (pinfunction "Shield_Shell") (pintype "passive"))
      (node (ref "J35") (pin "10") (pinfunction "TMDS_Data0_Shield_10") (pintype "passive"))
      (node (ref "J35") (pin "13") (pinfunction "TMDS_Clock_Shield_13") (pintype "passive"))
      (node (ref "J35") (pin "16") (pinfunction "DDC_/_CEC_Ground_/_HEAC_Shield_16") (pintype "passive"))
      (node (ref "J35") (pin "4") (pinfunction "TMDS_Data2_Shield_4") (pintype "passive"))
      (node (ref "J35") (pin "7") (pinfunction "TMDS_Data1_Shield_7") (pintype "passive"))
      (node (ref "J35") (pin "Shell") (pinfunction "Shield_Shell") (pintype "passive"))
      (node (ref "R162") (pin "2") (pinfunction "2_2") (pintype "passive"))
      (node (ref "R168") (pin "1") (pinfunction "1_1") (pintype "passive"))
      (node (ref "R174") (pin "1") (pinfunction "1_1") (pintype "passive"))
      (node (ref "VD14") (pin "K") (pinfunction "K_K") (pintype "passive"))
      (node (ref "VD15") (pin "K") (pinfunction "K_K") (pintype "passive"))
      (node (ref "VD16") (pin "K") (pinfunction "K_K") (pintype "passive"))
      (node (ref "VD17") (pin "K") (pinfunction "K_K") (pintype "passive"))
    )
    (net (code "60") (name "Net-(IC25-CSLEW)") (class "Default")
      (node (ref "C97") (pin "1") (pinfunction "1_1") (pintype "passive"))
      (node (ref "IC25") (pin "5") (pinfunction "CSLEW_5") (pintype "output"))
      (node (ref "R166") (pin "1") (pinfunction "1_1") (pintype "passive"))
      (node (ref "R168") (pin "2") (pinfunction "2_2") (pintype "passive"))
    )
    (net (code "61") (name "Net-(IC25-EN)") (class "Default")
      (node (ref "IC25") (pin "3") (pinfunction "EN_3") (pintype "input"))
      (node (ref "R164") (pin "1") (pinfunction "1_1") (pintype "passive"))
      (node (ref "R165") (pin "1") (pinfunction "1_1") (pintype "passive"))
      (node (ref "R167") (pin "1") (pinfunction "1_1") (pintype "passive"))
    )
    (net (code "62") (name "Net-(IC25-FAULT{slash})") (class "Default")
      (node (ref "IC25") (pin "4") (pinfunction "FAULT/_4") (pintype "output"))
      (node (ref "R169") (pin "1") (pinfunction "1_1") (pintype "passive"))
    )
    (net (code "63") (name "Net-(IC28-CSLEW)") (class "Default")
      (node (ref "C102") (pin "1") (pinfunction "1_1") (pintype "passive"))
      (node (ref "IC28") (pin "5") (pinfunction "CSLEW_5") (pintype "output"))
      (node (ref "R172") (pin "1") (pinfunction "1_1") (pintype "passive"))
      (node (ref "R174") (pin "2") (pinfunction "2_2") (pintype "passive"))
    )
    (net (code "64") (name "Net-(IC28-EN)") (class "Default")
      (node (ref "IC28") (pin "3") (pinfunction "EN_3") (pintype "input"))
      (node (ref "R171") (pin "1") (pinfunction "1_1") (pintype "passive"))
    )
    (net (code "65") (name "Net-(IC28-FAULT{slash})") (class "Default")
      (node (ref "IC28") (pin "4") (pinfunction "FAULT/_4") (pintype "output"))
      (node (ref "R173") (pin "2") (pinfunction "2_2") (pintype "passive"))
    )
    (net (code "66") (name "Net-(IC29-SSTX2+)") (class "Default")
      (node (ref "C107") (pin "1") (pinfunction "1_1") (pintype "passive"))
      (node (ref "IC29") (pin "13") (pinfunction "SSTX2+_13") (pintype "bidirectional"))
    )
    (net (code "67") (name "Net-(IC29-SSTX2-)") (class "Default")
      (node (ref "C105") (pin "1") (pinfunction "1_1") (pintype "passive"))
      (node (ref "IC29") (pin "14") (pinfunction "SSTX2-_14") (pintype "bidirectional"))
    )
    (net (code "68") (name "Net-(IC30-SSTX2+)") (class "Default")
      (node (ref "C108") (pin "1") (pinfunction "1_1") (pintype "passive"))
      (node (ref "IC30") (pin "13") (pinfunction "SSTX2+_13") (pintype "bidirectional"))
    )
    (net (code "69") (name "Net-(IC30-SSTX2-)") (class "Default")
      (node (ref "C106") (pin "1") (pinfunction "1_1") (pintype "passive"))
      (node (ref "IC30") (pin "14") (pinfunction "SSTX2-_14") (pintype "bidirectional"))
    )
    (net (code "70") (name "VCC3P3") (class "Default")
      (node (ref "C103") (pin "1") (pinfunction "1_1") (pintype "passive"))
      (node (ref "C104") (pin "1") (pinfunction "1_1") (pintype "passive"))
      (node (ref "C109") (pin "1") (pinfunction "1_1") (pintype "passive"))
      (node (ref "C110") (pin "1") (pinfunction "1_1") (pintype "passive"))
      (node (ref "IC26") (pin "9") (pinfunction "VCC_9") (pintype "power_in"))
      (node (ref "IC27") (pin "9") (pinfunction "VCC_9") (pintype "power_in"))
      (node (ref "IC29") (pin "17") (pinfunction "VDD_17") (pintype "power_in"))
      (node (ref "IC30") (pin "17") (pinfunction "VDD_17") (pintype "power_in"))
      (node (ref "R161") (pin "2") (pinfunction "2_2") (pintype "passive"))
    )
    (net (code "71") (name "VCC5P0") (class "Default")
      (node (ref "C102") (pin "2") (pinfunction "2_2") (pintype "passive"))
      (node (ref "C94") (pin "1") (pinfunction "1_1") (pintype "passive"))
      (node (ref "C97") (pin "2") (pinfunction "2_2") (pintype "passive"))
      (node (ref "C98") (pin "1") (pinfunction "1_1") (pintype "passive"))
      (node (ref "IC25") (pin "1") (pinfunction "VIN_1") (pintype "input"))
      (node (ref "IC28") (pin "1") (pinfunction "VIN_1") (pintype "input"))
      (node (ref "R163") (pin "2") (pinfunction "2_2") (pintype "passive"))
      (node (ref "R164") (pin "2") (pinfunction "2_2") (pintype "passive"))
      (node (ref "R170") (pin "2") (pinfunction "2_2") (pintype "passive"))
      (node (ref "R171") (pin "2") (pinfunction "2_2") (pintype "passive"))
      (node (ref "R173") (pin "1") (pinfunction "1_1") (pintype "passive"))
    )
    (net (code "72") (name "VCC5P0_HDMI") (class "Default")
      (node (ref "C100") (pin "1") (pinfunction "1_1") (pintype "passive"))
      (node (ref "C101") (pin "1") (pinfunction "1_1") (pintype "passive"))
      (node (ref "C99") (pin "1") (pinfunction "1_1") (pintype "passive"))
      (node (ref "IC28") (pin "6") (pinfunction "VOUT_6") (pintype "output"))
      (node (ref "J34") (pin "19") (pinfunction "+5V_Power_19") (pintype "passive"))
      (node (ref "J35") (pin "19") (pinfunction "+5V_Power_19") (pintype "passive"))
      (node (ref "R170") (pin "1") (pinfunction "1_1") (pintype "passive"))
      (node (ref "R172") (pin "2") (pinfunction "2_2") (pintype "passive"))
    )
    (net (code "73") (name "VCC5P0_USBS") (class "Default")
      (node (ref "C93") (pin "2") (pinfunction "2_2") (pintype "passive"))
      (node (ref "C95") (pin "1") (pinfunction "1_1") (pintype "passive"))
      (node (ref "C96") (pin "2") (pinfunction "2_2") (pintype "passive"))
      (node (ref "IC25") (pin "6") (pinfunction "VOUT_6") (pintype "output"))
      (node (ref "J33") (pin "1") (pinfunction "VBUS_1") (pintype "power_in"))
      (node (ref "J33") (pin "10") (pinfunction "VBUS_10") (pintype "power_in"))
      (node (ref "R163") (pin "1") (pinfunction "1_1") (pintype "passive"))
      (node (ref "R166") (pin "2") (pinfunction "2_2") (pintype "passive"))
    )
    (net (code "74") (name "unconnected-(IC29-SSRX1+-Pad10)") (class "Default")
      (node (ref "IC29") (pin "10") (pinfunction "SSRX1+_10") (pintype "bidirectional+no_connect"))
    )
    (net (code "75") (name "unconnected-(IC29-SSRX1--Pad11)") (class "Default")
      (node (ref "IC29") (pin "11") (pinfunction "SSRX1-_11") (pintype "bidirectional+no_connect"))
    )
    (net (code "76") (name "unconnected-(IC29-SSTX1+-Pad15)") (class "Default")
      (node (ref "IC29") (pin "15") (pinfunction "SSTX1+_15") (pintype "bidirectional+no_connect"))
    )
    (net (code "77") (name "unconnected-(IC29-SSTX1--Pad16)") (class "Default")
      (node (ref "IC29") (pin "16") (pinfunction "SSTX1-_16") (pintype "bidirectional+no_connect"))
    )
    (net (code "78") (name "unconnected-(IC30-SSRX1+-Pad10)") (class "Default")
      (node (ref "IC30") (pin "10") (pinfunction "SSRX1+_10") (pintype "bidirectional+no_connect"))
    )
    (net (code "79") (name "unconnected-(IC30-SSRX1--Pad11)") (class "Default")
      (node (ref "IC30") (pin "11") (pinfunction "SSRX1-_11") (pintype "bidirectional+no_connect"))
    )
    (net (code "80") (name "unconnected-(IC30-SSTX1+-Pad15)") (class "Default")
      (node (ref "IC30") (pin "15") (pinfunction "SSTX1+_15") (pintype "bidirectional+no_connect"))
    )
    (net (code "81") (name "unconnected-(IC30-SSTX1--Pad16)") (class "Default")
      (node (ref "IC30") (pin "16") (pinfunction "SSTX1-_16") (pintype "bidirectional+no_connect"))
    )
    (net (code "82") (name "unconnected-(J33-STDA_SSRX+-Pad6)") (class "Default")
      (node (ref "J33") (pin "6") (pinfunction "STDA_SSRX+_6") (pintype "bidirectional+no_connect"))
    )
    (net (code "83") (name "unconnected-(J33-STDA_SSRX--Pad5)") (class "Default")
      (node (ref "J33") (pin "5") (pinfunction "STDA_SSRX-_5") (pintype "bidirectional+no_connect"))
    )
    (net (code "84") (name "unconnected-(J33-STDA_SSTX+-Pad9)") (class "Default")
      (node (ref "J33") (pin "9") (pinfunction "STDA_SSTX+_9") (pintype "bidirectional+no_connect"))
    )
    (net (code "85") (name "unconnected-(J33-STDA_SSTX--Pad8)") (class "Default")
      (node (ref "J33") (pin "8") (pinfunction "STDA_SSTX-_8") (pintype "bidirectional+no_connect"))
    )
    (net (code "86") (name "unconnected-(J34-Utility_{slash}_HEAC+-Pad2)") (class "Default")
      (node (ref "J34") (pin "2") (pinfunction "Utility_/_HEAC+_2") (pintype "passive+no_connect"))
    )
    (net (code "87") (name "unconnected-(J35-Utility_{slash}_HEAC+-Pad2)") (class "Default")
      (node (ref "J35") (pin "2") (pinfunction "Utility_/_HEAC+_2") (pintype "passive+no_connect"))
    )
  )
)
